# GeneralScheme.net
KiCad netlist of a schematic drawn in Altium Designer
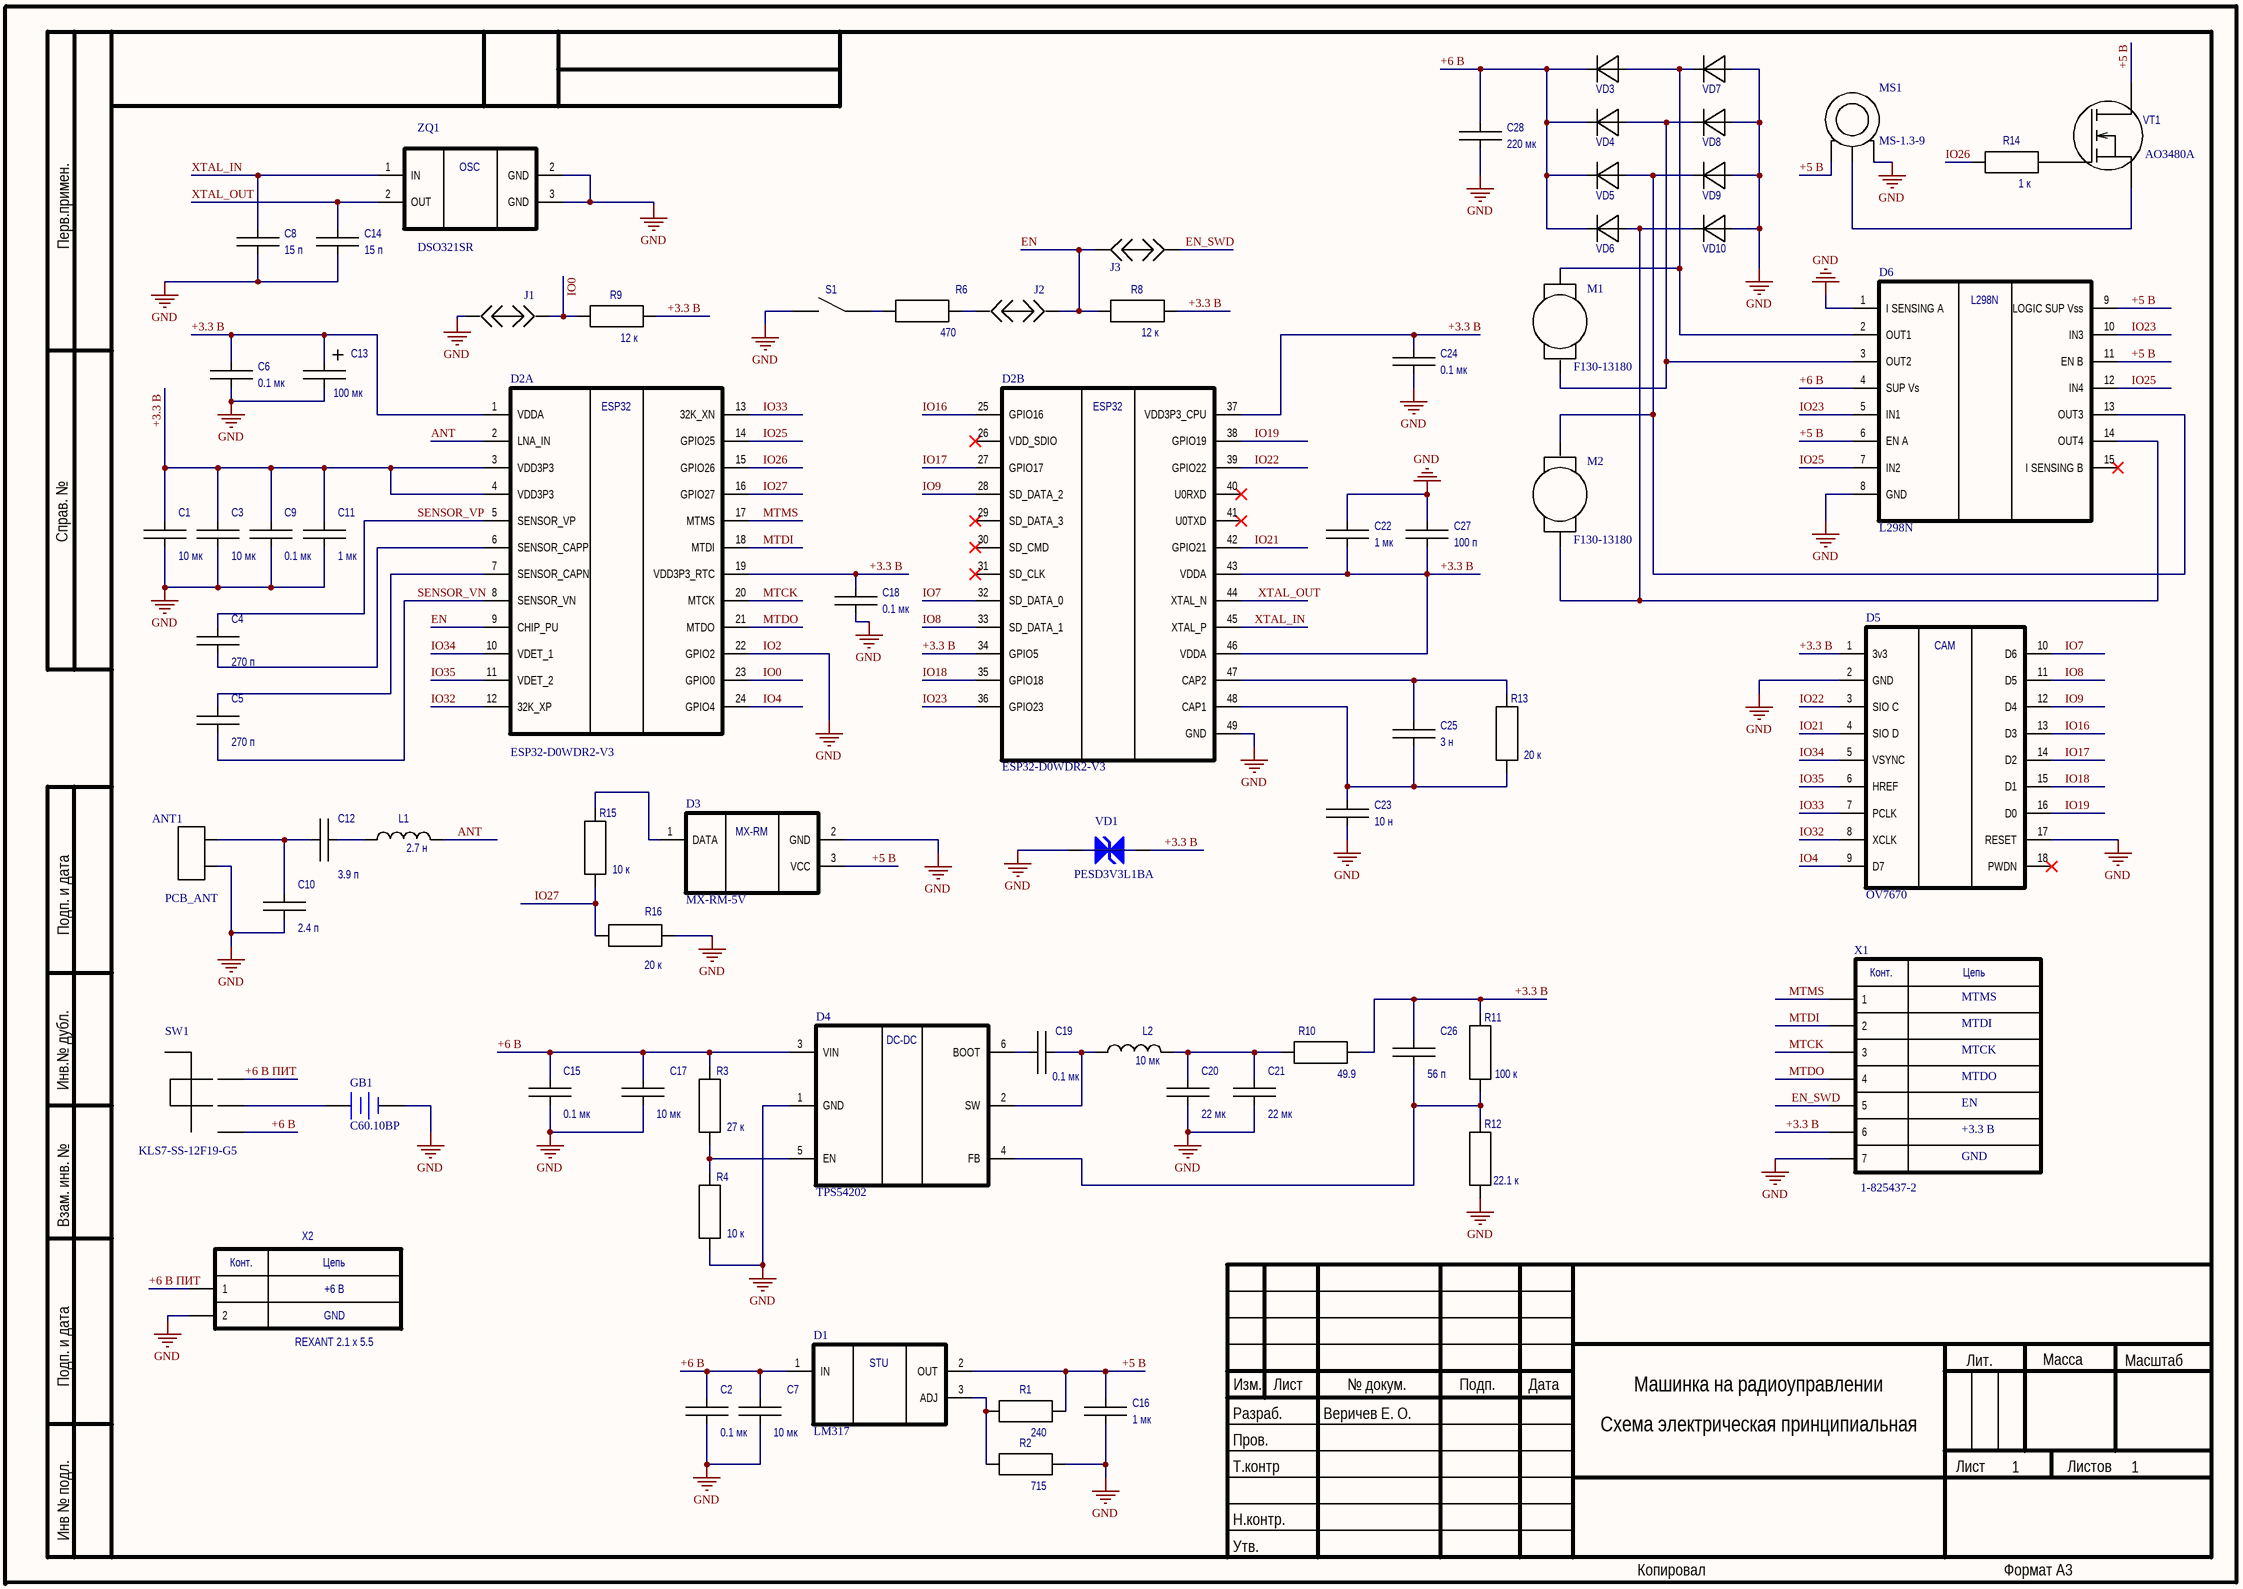
[diagram p0: GeneralScheme.SchDoc]

(export (version "E")
  (design (tool "Eeschema 10.0.6"))
  (components
    (comp (ref "ANT1") (value "PCB_ANT") (libsource (lib "IVT_LIB") (part "PCB_ant")))
    (comp (ref "C1")
      (value "10 мк")
      (fields (field (name "Comment") "10 мкФ ±* * * *, *"))
      (libsource (lib "IVT_LIB") (part "C - Конденсатор"))
    )
    (comp (ref "C2")
      (value "0.1 мк")
      (fields (field (name "Comment") "0.1 мкФ ±* * * *, *"))
      (libsource (lib "IVT_LIB") (part "C - Конденсатор"))
    )
    (comp (ref "C3")
      (value "10 мк")
      (fields (field (name "Comment") "10 мкФ ±* * * *, *"))
      (libsource (lib "IVT_LIB") (part "C - Конденсатор"))
    )
    (comp (ref "C4")
      (value "270 п")
      (fields (field (name "Comment") "270 пФ ±* * * *, *"))
      (libsource (lib "IVT_LIB") (part "C - Конденсатор"))
    )
    (comp (ref "C5")
      (value "270 п")
      (fields (field (name "Comment") "270 пФ ±* * * *, *"))
      (libsource (lib "IVT_LIB") (part "C - Конденсатор"))
    )
    (comp (ref "C6")
      (value "0.1 мк")
      (fields (field (name "Comment") "0.1 мкФ ±* * * *, *"))
      (libsource (lib "IVT_LIB") (part "C - Конденсатор"))
    )
    (comp (ref "C7")
      (value "10 мк")
      (fields (field (name "Comment") "10 мкФ ±* * * *, *"))
      (libsource (lib "IVT_LIB") (part "C - Конденсатор"))
    )
    (comp (ref "C8")
      (value "15 п")
      (fields (field (name "Comment") "15 пФ ±* * * *, *"))
      (libsource (lib "IVT_LIB") (part "C - Конденсатор"))
    )
    (comp (ref "C9")
      (value "0.1 мк")
      (fields (field (name "Comment") "0.1 мкФ ±* * * *, *"))
      (libsource (lib "IVT_LIB") (part "C - Конденсатор"))
    )
    (comp (ref "C10")
      (value "2.4 п")
      (fields (field (name "Comment") "2.4 пФ ±* * * *, *"))
      (libsource (lib "IVT_LIB") (part "C - Конденсатор"))
    )
    (comp (ref "C11")
      (value "1 мк")
      (fields (field (name "Comment") "1 мкФ ±* * * *, *"))
      (libsource (lib "IVT_LIB") (part "C - Конденсатор"))
    )
    (comp (ref "C12")
      (value "3.9 п")
      (fields (field (name "Comment") "3.9 пФ ±* * * *, *"))
      (libsource (lib "IVT_LIB") (part "C - Конденсатор"))
    )
    (comp (ref "C13")
      (value "100 мк")
      (fields (field (name "Comment") "100 мкФ ±* * * *, *"))
      (libsource (lib "IVT_LIB") (part "C+ - Конденсатор электролитический"))
    )
    (comp (ref "C14")
      (value "15 п")
      (fields (field (name "Comment") "15 пФ ±* * * *, *"))
      (libsource (lib "IVT_LIB") (part "C - Конденсатор"))
    )
    (comp (ref "C15")
      (value "0.1 мк")
      (fields (field (name "Comment") "0.1 мкФ ±* * * *, *"))
      (libsource (lib "IVT_LIB") (part "C - Конденсатор"))
    )
    (comp (ref "C16")
      (value "1 мк")
      (fields (field (name "Comment") "1 мкФ ±* * * *, *"))
      (libsource (lib "IVT_LIB") (part "C - Конденсатор"))
    )
    (comp (ref "C17")
      (value "10 мк")
      (fields (field (name "Comment") "10 мкФ ±* * * *, *"))
      (libsource (lib "IVT_LIB") (part "C - Конденсатор"))
    )
    (comp (ref "C18")
      (value "0.1 мк")
      (fields (field (name "Comment") "0.1 мкФ ±* * * *, *"))
      (libsource (lib "IVT_LIB") (part "C - Конденсатор"))
    )
    (comp (ref "C19")
      (value "0.1 мк")
      (fields (field (name "Comment") "0.1 мкФ ±* * * *, *"))
      (libsource (lib "IVT_LIB") (part "C - Конденсатор"))
    )
    (comp (ref "C20")
      (value "22 мк")
      (fields (field (name "Comment") "22 мкФ ±* * * *, *"))
      (libsource (lib "IVT_LIB") (part "C - Конденсатор"))
    )
    (comp (ref "C21")
      (value "22 мк")
      (fields (field (name "Comment") "22 мкФ ±* * * *, *"))
      (libsource (lib "IVT_LIB") (part "C - Конденсатор"))
    )
    (comp (ref "C22")
      (value "1 мк")
      (fields (field (name "Comment") "1 мкФ ±* * * *, *"))
      (libsource (lib "IVT_LIB") (part "C - Конденсатор"))
    )
    (comp (ref "C23")
      (value "10 н")
      (fields (field (name "Comment") "10 нФ ±* * * *, *"))
      (libsource (lib "IVT_LIB") (part "C - Конденсатор"))
    )
    (comp (ref "C24")
      (value "0.1 мк")
      (fields (field (name "Comment") "0.1 мкФ ±* * * *, *"))
      (libsource (lib "IVT_LIB") (part "C - Конденсатор"))
    )
    (comp (ref "C25")
      (value "3 н")
      (fields (field (name "Comment") "3 нФ ±* * * *, *"))
      (libsource (lib "IVT_LIB") (part "C - Конденсатор"))
    )
    (comp (ref "C26")
      (value "56 п")
      (fields (field (name "Comment") "56 пФ ±* * * *, *"))
      (libsource (lib "IVT_LIB") (part "C - Конденсатор"))
    )
    (comp (ref "C27")
      (value "100 п")
      (fields (field (name "Comment") "100 пФ ±* * * *, *"))
      (libsource (lib "IVT_LIB") (part "C - Конденсатор"))
    )
    (comp (ref "C28")
      (value "220 мк")
      (fields (field (name "Comment") "220 мкФ ±* * * *, *"))
      (libsource (lib "IVT_LIB") (part "C - Конденсатор"))
    )
    (comp (ref "D1") (value "LM317") (libsource (lib "IVT_LIB") (part "LM317")))
    (comp (ref "D2") (value "ESP32-D0WDR2-V3") (libsource (lib "IVT_LIB") (part "ESP32-D0WDR2-V3")))
    (comp (ref "D3") (value "MX-RM-5V") (libsource (lib "IVT_LIB") (part "MX-RM-5V_reciever_module")))
    (comp (ref "D4") (value "TPS54202") (libsource (lib "IVT_LIB") (part "TPS54202_DCDC")))
    (comp (ref "D5") (value "OV7670") (libsource (lib "IVT_LIB") (part "OV7670_module")))
    (comp (ref "D6") (value "L298N") (libsource (lib "IVT_LIB") (part "L298N")))
    (comp (ref "GB1")
      (value "C60.10BP")
      (footprint "BAT-2")
      (description "Multicell Battery")
      (fields (field (name "PUBLISHER") "Altium Limited"))
      (libsource (lib "Miscellaneous Devices") (part "Battery"))
    )
    (comp (ref "J1") (value "Jumper") (libsource (lib "IVT_LIB") (part "Jumper")))
    (comp (ref "J2") (value "Jumper") (libsource (lib "IVT_LIB") (part "Jumper")))
    (comp (ref "J3") (value "Jumper") (libsource (lib "IVT_LIB") (part "Jumper")))
    (comp (ref "L1") (value "2.7 н") (libsource (lib "IVT_LIB") (part "L - induct_my")))
    (comp (ref "L2") (value "10 мк") (libsource (lib "IVT_LIB") (part "L - induct_my")))
    (comp (ref "M1") (value "F130-13180") (libsource (lib "IVT_LIB") (part "F130-13180")))
    (comp (ref "M2") (value "F130-13180") (libsource (lib "IVT_LIB") (part "F130-13180")))
    (comp (ref "MS1") (value "MS-1.3-9") (libsource (lib "IVT_LIB") (part "MS-1.3-9")))
    (comp (ref "R1")
      (value "240")
      (fields (field (name "Comment") "240Ом ±* *, *"))
      (libsource (lib "IVT_LIB") (part "R - Резистор"))
    )
    (comp (ref "R2")
      (value "715")
      (fields (field (name "Comment") "715Ом ±* *, *"))
      (libsource (lib "IVT_LIB") (part "R - Резистор"))
    )
    (comp (ref "R3")
      (value "27 к")
      (fields (field (name "Comment") "27 кОм ±* *, *"))
      (libsource (lib "IVT_LIB") (part "R - Резистор"))
    )
    (comp (ref "R4")
      (value "10 к")
      (fields (field (name "Comment") "10 кОм ±* *, *"))
      (libsource (lib "IVT_LIB") (part "R - Резистор"))
    )
    (comp (ref "R6")
      (value "470")
      (fields (field (name "Comment") "470Ом ±* *, *"))
      (libsource (lib "IVT_LIB") (part "R - Резистор"))
    )
    (comp (ref "R8")
      (value "12 к")
      (fields (field (name "Comment") "12 кОм ±* *, *"))
      (libsource (lib "IVT_LIB") (part "R - Резистор"))
    )
    (comp (ref "R9")
      (value "12 к")
      (fields (field (name "Comment") "12 кОм ±* *, *"))
      (libsource (lib "IVT_LIB") (part "R - Резистор"))
    )
    (comp (ref "R10")
      (value "49.9")
      (fields (field (name "Comment") "49.9Ом ±* *, *"))
      (libsource (lib "IVT_LIB") (part "R - Резистор"))
    )
    (comp (ref "R11")
      (value "100 к")
      (fields (field (name "Comment") "100 кОм ±* *, *"))
      (libsource (lib "IVT_LIB") (part "R - Резистор"))
    )
    (comp (ref "R12")
      (value "22.1 к")
      (fields (field (name "Comment") "22.1 кОм ±* *, *"))
      (libsource (lib "IVT_LIB") (part "R - Резистор"))
    )
    (comp (ref "R13")
      (value "20 к")
      (fields (field (name "Comment") "20 кОм ±* *, *"))
      (libsource (lib "IVT_LIB") (part "R - Резистор"))
    )
    (comp (ref "R14")
      (value "1 к")
      (fields (field (name "Comment") "1 кОм ±* *, *"))
      (libsource (lib "IVT_LIB") (part "R - Резистор"))
    )
    (comp (ref "R15")
      (value "10 к")
      (fields (field (name "Comment") "10 кОм ±* *, *"))
      (libsource (lib "IVT_LIB") (part "R - Резистор"))
    )
    (comp (ref "R16")
      (value "20 к")
      (fields (field (name "Comment") "20 кОм ±* *, *"))
      (libsource (lib "IVT_LIB") (part "R - Резистор"))
    )
    (comp (ref "S1")
      (value "Тактильный переключатель KLS7-TS6604-4.3-180-B KLS")
      (fields (field (name "PARTNUMBER") "KLS7-TS6604-4.3-180-B"))
      (libsource (lib "IVT_LIB") (part "S - Кнопка тактовая"))
    )
    (comp (ref "SW1") (value "KLS7-SS-12F19-G5") (libsource (lib "IVT_LIB") (part "Switch")))
    (comp (ref "VD1")
      (value "PESD3V3L1BA")
      (footprint "DIODE-0.7")
      (description "Zener Diode")
      (fields (field (name "PUBLISHER") "Altium Limited"))
      (libsource (lib "Miscellaneous Devices") (part "D Zener"))
    )
    (comp (ref "VD2")
      (value "D Zener")
      (footprint "DIODE-0.7")
      (description "Zener Diode")
      (fields (field (name "PUBLISHER") "Altium Limited"))
      (libsource (lib "Miscellaneous Devices") (part "D Zener"))
    )
    (comp (ref "VD3") (value "MBR0540") (libsource (lib "IVT_LIB") (part "VD - Диод обычный")))
    (comp (ref "VD4") (value "MBR0540") (libsource (lib "IVT_LIB") (part "VD - Диод обычный")))
    (comp (ref "VD5") (value "MBR0540") (libsource (lib "IVT_LIB") (part "VD - Диод обычный")))
    (comp (ref "VD6") (value "MBR0540") (libsource (lib "IVT_LIB") (part "VD - Диод обычный")))
    (comp (ref "VD7") (value "MBR0540") (libsource (lib "IVT_LIB") (part "VD - Диод обычный")))
    (comp (ref "VD8") (value "MBR0540") (libsource (lib "IVT_LIB") (part "VD - Диод обычный")))
    (comp (ref "VD9") (value "MBR0540") (libsource (lib "IVT_LIB") (part "VD - Диод обычный")))
    (comp (ref "VD10") (value "MBR0540") (libsource (lib "IVT_LIB") (part "VD - Диод обычный")))
    (comp (ref "VT1")
      (value "AO3480A")
      (description "VT")
      (libsource (lib "IVT_LIB") (part "VT - Полевой транзистор N канал (MOSFET_N)"))
    )
    (comp (ref "X1")
      (value "1-825437-2")
      (fields
        (field (name "PARAMETER 7") "GND")
        (field (name "PARAMETER 6") "+3.3 В")
        (field (name "PARAMETER 2") "MTDI")
        (field (name "PARAMETER 5") "EN")
        (field (name "PARAMETER 4") "MTDO")
        (field (name "PARAMETER 3") "MTCK")
        (field (name "PARAMETER 1") "MTMS")
      )
      (libsource (lib "IVT_LIB") (part "X - контактное поле х7"))
    )
    (comp (ref "X2")
      (value "REXANT 2.1 х 5.5")
      (fields (field (name "1") "+6 В") (field (name "2") "GND"))
      (libsource (lib "IVT_LIB") (part "X - Контактное поле х2"))
    )
    (comp (ref "ZQ1") (value "DSO321SR") (libsource (lib "IVT_LIB") (part "DSO321SR_oscill")))
  )
  (nets
    (net (code "1") (name "/+3.3 В") (class "Default")
      (node (ref "C1") (pin "2") (pinfunction "2_2") (pintype "passive"))
      (node (ref "C11") (pin "2") (pinfunction "2_2") (pintype "passive"))
      (node (ref "C13") (pin "1") (pinfunction "1_1") (pintype "passive"))
      (node (ref "C18") (pin "2") (pinfunction "2_2") (pintype "passive"))
      (node (ref "C22") (pin "1") (pinfunction "1_1") (pintype "passive"))
      (node (ref "C24") (pin "2") (pinfunction "2_2") (pintype "passive"))
      (node (ref "C26") (pin "2") (pinfunction "2_2") (pintype "passive"))
      (node (ref "C27") (pin "1") (pinfunction "1_1") (pintype "passive"))
      (node (ref "C3") (pin "2") (pinfunction "2_2") (pintype "passive"))
      (node (ref "C6") (pin "2") (pinfunction "2_2") (pintype "passive"))
      (node (ref "C9") (pin "2") (pinfunction "2_2") (pintype "passive"))
      (node (ref "D2") (pin "1") (pinfunction "VDDA_1") (pintype "passive"))
      (node (ref "D2") (pin "19") (pinfunction "VDD3P3_RTC_19") (pintype "passive"))
      (node (ref "D2") (pin "3") (pinfunction "VDD3P3_3") (pintype "passive"))
      (node (ref "D2") (pin "34") (pinfunction "GPIO5_34") (pintype "passive"))
      (node (ref "D2") (pin "37") (pinfunction "VDD3P3_CPU_37") (pintype "passive"))
      (node (ref "D2") (pin "4") (pinfunction "VDD3P3_4") (pintype "passive"))
      (node (ref "D2") (pin "43") (pinfunction "VDDA_43") (pintype "passive"))
      (node (ref "D2") (pin "46") (pinfunction "VDDA_46") (pintype "passive"))
      (node (ref "D5") (pin "1") (pinfunction "3v3_1") (pintype "passive"))
      (node (ref "R10") (pin "1") (pinfunction "1_1") (pintype "passive"))
      (node (ref "R11") (pin "2") (pinfunction "2_2") (pintype "passive"))
      (node (ref "R8") (pin "2") (pinfunction "2_2") (pintype "passive"))
      (node (ref "R9") (pin "2") (pinfunction "2_2") (pintype "passive"))
      (node (ref "VD2") (pin "1") (pinfunction "A_1") (pintype "passive"))
      (node (ref "X1") (pin "6") (pinfunction "6_6") (pintype "passive"))
    )
    (net (code "2") (name "/+5 В") (class "Default")
      (node (ref "C16") (pin "2") (pinfunction "2_2") (pintype "passive"))
      (node (ref "D1") (pin "2") (pinfunction "OUT_2") (pintype "passive"))
      (node (ref "D3") (pin "3") (pinfunction "VCC_3") (pintype "passive"))
      (node (ref "D6") (pin "11") (pinfunction "EN_B_11") (pintype "passive"))
      (node (ref "D6") (pin "6") (pinfunction "EN_A_6") (pintype "passive"))
      (node (ref "D6") (pin "9") (pinfunction "LOGIC_SUP_Vss_9") (pintype "passive"))
      (node (ref "MS1") (pin "1") (pinfunction "VDD_1") (pintype "passive"))
      (node (ref "R1") (pin "1") (pinfunction "1_1") (pintype "passive"))
      (node (ref "VT1") (pin "1") (pintype "passive"))
    )
    (net (code "3") (name "/+6 В") (class "Default")
      (node (ref "C15") (pin "2") (pinfunction "2_2") (pintype "passive"))
      (node (ref "C17") (pin "2") (pinfunction "2_2") (pintype "passive"))
      (node (ref "C2") (pin "2") (pinfunction "2_2") (pintype "passive"))
      (node (ref "C28") (pin "2") (pinfunction "2_2") (pintype "passive"))
      (node (ref "C7") (pin "2") (pinfunction "2_2") (pintype "passive"))
      (node (ref "D1") (pin "1") (pinfunction "IN_1") (pintype "passive"))
      (node (ref "D4") (pin "3") (pinfunction "VIN_3") (pintype "passive"))
      (node (ref "D6") (pin "4") (pinfunction "SUP_Vs_4") (pintype "passive"))
      (node (ref "R3") (pin "2") (pinfunction "2_2") (pintype "passive"))
      (node (ref "SW1") (pin "3") (pinfunction "3_3") (pintype "passive"))
      (node (ref "VD3") (pin "1") (pinfunction "C_1") (pintype "passive"))
      (node (ref "VD4") (pin "1") (pinfunction "C_1") (pintype "passive"))
      (node (ref "VD5") (pin "1") (pinfunction "C_1") (pintype "passive"))
      (node (ref "VD6") (pin "1") (pinfunction "C_1") (pintype "passive"))
    )
    (net (code "4") (name "/+6 В ПИТ") (class "Default")
      (node (ref "SW1") (pin "1") (pinfunction "1_1") (pintype "passive"))
      (node (ref "X2") (pin "1") (pinfunction "1_1") (pintype "passive"))
    )
    (net (code "5") (name "/ANT") (class "Default")
      (node (ref "D2") (pin "2") (pinfunction "LNA_IN_2") (pintype "passive"))
      (node (ref "L1") (pin "1") (pinfunction "1_1") (pintype "passive"))
    )
    (net (code "6") (name "/EN") (class "Default")
      (node (ref "D2") (pin "9") (pinfunction "CHIP_PU_9") (pintype "passive"))
      (node (ref "J2") (pin "2") (pinfunction "2_2") (pintype "passive"))
      (node (ref "J3") (pin "2") (pinfunction "2_2") (pintype "passive"))
      (node (ref "R8") (pin "1") (pinfunction "1_1") (pintype "passive"))
    )
    (net (code "7") (name "/EN_SWD") (class "Default")
      (node (ref "J3") (pin "1") (pinfunction "1_1") (pintype "passive"))
      (node (ref "X1") (pin "5") (pinfunction "5_5") (pintype "passive"))
    )
    (net (code "8") (name "/IO0") (class "Default")
      (node (ref "D2") (pin "23") (pinfunction "GPIO0_23") (pintype "passive"))
      (node (ref "J1") (pin "2") (pinfunction "2_2") (pintype "passive"))
      (node (ref "R9") (pin "1") (pinfunction "1_1") (pintype "passive"))
    )
    (net (code "9") (name "/IO4") (class "Default")
      (node (ref "D2") (pin "24") (pinfunction "GPIO4_24") (pintype "passive"))
      (node (ref "D5") (pin "9") (pinfunction "D7_9") (pintype "passive"))
    )
    (net (code "10") (name "/IO7") (class "Default")
      (node (ref "D2") (pin "32") (pinfunction "SD_DATA_0_32") (pintype "passive"))
      (node (ref "D5") (pin "10") (pinfunction "D6_10") (pintype "passive"))
    )
    (net (code "11") (name "/IO8") (class "Default")
      (node (ref "D2") (pin "33") (pinfunction "SD_DATA_1_33") (pintype "passive"))
      (node (ref "D5") (pin "11") (pinfunction "D5_11") (pintype "passive"))
    )
    (net (code "12") (name "/IO9") (class "Default")
      (node (ref "D2") (pin "28") (pinfunction "SD_DATA_2_28") (pintype "passive"))
      (node (ref "D5") (pin "12") (pinfunction "D4_12") (pintype "passive"))
    )
    (net (code "13") (name "/IO16") (class "Default")
      (node (ref "D2") (pin "25") (pinfunction "GPIO16_25") (pintype "passive"))
      (node (ref "D5") (pin "13") (pinfunction "D3_13") (pintype "passive"))
    )
    (net (code "14") (name "/IO17") (class "Default")
      (node (ref "D2") (pin "27") (pinfunction "GPIO17_27") (pintype "passive"))
      (node (ref "D5") (pin "14") (pinfunction "D2_14") (pintype "passive"))
    )
    (net (code "15") (name "/IO18") (class "Default")
      (node (ref "D2") (pin "35") (pinfunction "GPIO18_35") (pintype "passive"))
      (node (ref "D5") (pin "15") (pinfunction "D1_15") (pintype "passive"))
    )
    (net (code "16") (name "/IO19") (class "Default")
      (node (ref "D2") (pin "38") (pinfunction "GPIO19_38") (pintype "passive"))
      (node (ref "D5") (pin "16") (pinfunction "D0_16") (pintype "passive"))
    )
    (net (code "17") (name "/IO21") (class "Default")
      (node (ref "D2") (pin "42") (pinfunction "GPIO21_42") (pintype "passive"))
      (node (ref "D5") (pin "4") (pinfunction "SIO_D_4") (pintype "passive"))
    )
    (net (code "18") (name "/IO22") (class "Default")
      (node (ref "D2") (pin "39") (pinfunction "GPIO22_39") (pintype "passive"))
      (node (ref "D5") (pin "3") (pinfunction "SIO_C_3") (pintype "passive"))
    )
    (net (code "19") (name "/IO23") (class "Default")
      (node (ref "D2") (pin "36") (pinfunction "GPIO23_36") (pintype "passive"))
      (node (ref "D6") (pin "10") (pinfunction "IN3_10") (pintype "passive"))
      (node (ref "D6") (pin "5") (pinfunction "IN1_5") (pintype "passive"))
    )
    (net (code "20") (name "/IO25") (class "Default")
      (node (ref "D2") (pin "14") (pinfunction "GPIO25_14") (pintype "passive"))
      (node (ref "D6") (pin "12") (pinfunction "IN4_12") (pintype "passive"))
      (node (ref "D6") (pin "7") (pinfunction "IN2_7") (pintype "passive"))
    )
    (net (code "21") (name "/IO26") (class "Default")
      (node (ref "D2") (pin "15") (pinfunction "GPIO26_15") (pintype "passive"))
      (node (ref "R14") (pin "1") (pinfunction "1_1") (pintype "passive"))
    )
    (net (code "22") (name "/IO27") (class "Default")
      (node (ref "D2") (pin "16") (pinfunction "GPIO27_16") (pintype "passive"))
      (node (ref "R15") (pin "1") (pinfunction "1_1") (pintype "passive"))
      (node (ref "R16") (pin "2") (pinfunction "2_2") (pintype "passive"))
    )
    (net (code "23") (name "/IO32") (class "Default")
      (node (ref "D2") (pin "12") (pinfunction "32K_XP_12") (pintype "passive"))
      (node (ref "D5") (pin "8") (pinfunction "XCLK_8") (pintype "passive"))
    )
    (net (code "24") (name "/IO33") (class "Default")
      (node (ref "D2") (pin "13") (pinfunction "32K_XN_13") (pintype "passive"))
      (node (ref "D5") (pin "7") (pinfunction "PCLK_7") (pintype "passive"))
    )
    (net (code "25") (name "/IO34") (class "Default")
      (node (ref "D2") (pin "10") (pinfunction "VDET_1_10") (pintype "passive"))
      (node (ref "D5") (pin "5") (pinfunction "VSYNC_5") (pintype "passive"))
    )
    (net (code "26") (name "/IO35") (class "Default")
      (node (ref "D2") (pin "11") (pinfunction "VDET_2_11") (pintype "passive"))
      (node (ref "D5") (pin "6") (pinfunction "HREF_6") (pintype "passive"))
    )
    (net (code "27") (name "/MTCK") (class "Default")
      (node (ref "D2") (pin "20") (pinfunction "MTCK_20") (pintype "passive"))
      (node (ref "X1") (pin "3") (pinfunction "3_3") (pintype "passive"))
    )
    (net (code "28") (name "/MTDI") (class "Default")
      (node (ref "D2") (pin "18") (pinfunction "MTDI_18") (pintype "passive"))
      (node (ref "X1") (pin "2") (pinfunction "2_2") (pintype "passive"))
    )
    (net (code "29") (name "/MTDO") (class "Default")
      (node (ref "D2") (pin "21") (pinfunction "MTDO_21") (pintype "passive"))
      (node (ref "X1") (pin "4") (pinfunction "4_4") (pintype "passive"))
    )
    (net (code "30") (name "/MTMS") (class "Default")
      (node (ref "D2") (pin "17") (pinfunction "MTMS_17") (pintype "passive"))
      (node (ref "X1") (pin "1") (pinfunction "1_1") (pintype "passive"))
    )
    (net (code "31") (name "/SENSOR_VN") (class "Default")
      (node (ref "C5") (pin "1") (pinfunction "1_1") (pintype "passive"))
      (node (ref "D2") (pin "8") (pinfunction "SENSOR_VN_8") (pintype "passive"))
    )
    (net (code "32") (name "/SENSOR_VP") (class "Default")
      (node (ref "C4") (pin "2") (pinfunction "2_2") (pintype "passive"))
      (node (ref "D2") (pin "5") (pinfunction "SENSOR_VP_5") (pintype "passive"))
    )
    (net (code "33") (name "/XTAL_IN") (class "Default")
      (node (ref "C8") (pin "2") (pinfunction "2_2") (pintype "passive"))
      (node (ref "D2") (pin "45") (pinfunction "XTAL_P_45") (pintype "passive"))
      (node (ref "ZQ1") (pin "1") (pinfunction "IN_1") (pintype "passive"))
    )
    (net (code "34") (name "/XTAL_OUT") (class "Default")
      (node (ref "C14") (pin "2") (pinfunction "2_2") (pintype "passive"))
      (node (ref "D2") (pin "44") (pinfunction "XTAL_N_44") (pintype "passive"))
      (node (ref "ZQ1") (pin "2") (pinfunction "OUT_2") (pintype "passive"))
    )
    (net (code "35") (name "GND") (class "Default")
      (node (ref "ANT1") (pin "2") (pinfunction "2_2") (pintype "passive"))
      (node (ref "C1") (pin "1") (pinfunction "1_1") (pintype "passive"))
      (node (ref "C10") (pin "1") (pinfunction "1_1") (pintype "passive"))
      (node (ref "C11") (pin "1") (pinfunction "1_1") (pintype "passive"))
      (node (ref "C13") (pin "2") (pinfunction "2_2") (pintype "passive"))
      (node (ref "C14") (pin "1") (pinfunction "1_1") (pintype "passive"))
      (node (ref "C15") (pin "1") (pinfunction "1_1") (pintype "passive"))
      (node (ref "C16") (pin "1") (pinfunction "1_1") (pintype "passive"))
      (node (ref "C17") (pin "1") (pinfunction "1_1") (pintype "passive"))
      (node (ref "C18") (pin "1") (pinfunction "1_1") (pintype "passive"))
      (node (ref "C2") (pin "1") (pinfunction "1_1") (pintype "passive"))
      (node (ref "C20") (pin "1") (pinfunction "1_1") (pintype "passive"))
      (node (ref "C21") (pin "1") (pinfunction "1_1") (pintype "passive"))
      (node (ref "C22") (pin "2") (pinfunction "2_2") (pintype "passive"))
      (node (ref "C23") (pin "1") (pinfunction "1_1") (pintype "passive"))
      (node (ref "C24") (pin "1") (pinfunction "1_1") (pintype "passive"))
      (node (ref "C27") (pin "2") (pinfunction "2_2") (pintype "passive"))
      (node (ref "C28") (pin "1") (pinfunction "1_1") (pintype "passive"))
      (node (ref "C3") (pin "1") (pinfunction "1_1") (pintype "passive"))
      (node (ref "C6") (pin "1") (pinfunction "1_1") (pintype "passive"))
      (node (ref "C7") (pin "1") (pinfunction "1_1") (pintype "passive"))
      (node (ref "C8") (pin "1") (pinfunction "1_1") (pintype "passive"))
      (node (ref "C9") (pin "1") (pinfunction "1_1") (pintype "passive"))
      (node (ref "D2") (pin "22") (pinfunction "GPIO2_22") (pintype "passive"))
      (node (ref "D2") (pin "49") (pinfunction "GND_49") (pintype "passive"))
      (node (ref "D3") (pin "2") (pinfunction "GND_2") (pintype "passive"))
      (node (ref "D4") (pin "1") (pinfunction "GND_1") (pintype "passive"))
      (node (ref "D5") (pin "17") (pinfunction "RESET_17") (pintype "passive"))
      (node (ref "D5") (pin "2") (pinfunction "GND_2") (pintype "passive"))
      (node (ref "D6") (pin "1") (pinfunction "I_SENSING_A_1") (pintype "passive"))
      (node (ref "D6") (pin "8") (pinfunction "GND_8") (pintype "passive"))
      (node (ref "GB1") (pin "2") (pinfunction "-_2") (pintype "passive"))
      (node (ref "J1") (pin "1") (pinfunction "1_1") (pintype "passive"))
      (node (ref "MS1") (pin "2") (pinfunction "GND_2") (pintype "passive"))
      (node (ref "R12") (pin "1") (pinfunction "1_1") (pintype "passive"))
      (node (ref "R16") (pin "1") (pinfunction "1_1") (pintype "passive"))
      (node (ref "R2") (pin "1") (pinfunction "1_1") (pintype "passive"))
      (node (ref "R4") (pin "1") (pinfunction "1_1") (pintype "passive"))
      (node (ref "S1") (pin "4") (pinfunction "4_4") (pintype "passive"))
      (node (ref "VD1") (pin "1") (pinfunction "A_1") (pintype "passive"))
      (node (ref "VD10") (pin "1") (pinfunction "A_1") (pintype "passive"))
      (node (ref "VD7") (pin "1") (pinfunction "A_1") (pintype "passive"))
      (node (ref "VD8") (pin "1") (pinfunction "A_1") (pintype "passive"))
      (node (ref "VD9") (pin "1") (pinfunction "A_1") (pintype "passive"))
      (node (ref "X1") (pin "7") (pinfunction "7_7") (pintype "passive"))
      (node (ref "X2") (pin "2") (pinfunction "2_2") (pintype "passive"))
      (node (ref "ZQ1") (pin "2") (pinfunction "GND_2") (pintype "passive"))
      (node (ref "ZQ1") (pin "3") (pinfunction "GND_3") (pintype "passive"))
    )
    (net (code "36") (name "Net-(ANT1-Pad1)") (class "Default")
      (node (ref "ANT1") (pin "1") (pinfunction "1_1") (pintype "passive"))
      (node (ref "C10") (pin "2") (pinfunction "2_2") (pintype "passive"))
      (node (ref "C12") (pin "2") (pinfunction "2_2") (pintype "passive"))
    )
    (net (code "37") (name "Net-(C12-Pad1)") (class "Default")
      (node (ref "C12") (pin "1") (pinfunction "1_1") (pintype "passive"))
      (node (ref "L1") (pin "2") (pinfunction "2_2") (pintype "passive"))
    )
    (net (code "38") (name "Net-(C20-Pad2)") (class "Default")
      (node (ref "C20") (pin "2") (pinfunction "2_2") (pintype "passive"))
      (node (ref "C21") (pin "2") (pinfunction "2_2") (pintype "passive"))
      (node (ref "L2") (pin "1") (pinfunction "1_1") (pintype "passive"))
      (node (ref "R10") (pin "2") (pinfunction "2_2") (pintype "passive"))
    )
    (net (code "39") (name "Net-(D1-ADJ)") (class "Default")
      (node (ref "D1") (pin "3") (pinfunction "ADJ_3") (pintype "passive"))
      (node (ref "R1") (pin "2") (pinfunction "2_2") (pintype "passive"))
      (node (ref "R2") (pin "2") (pinfunction "2_2") (pintype "passive"))
    )
    (net (code "40") (name "Net-(D2A-SENSOR_CAPN)") (class "Default")
      (node (ref "C5") (pin "2") (pinfunction "2_2") (pintype "passive"))
      (node (ref "D2") (pin "7") (pinfunction "SENSOR_CAPN_7") (pintype "passive"))
    )
    (net (code "41") (name "Net-(D2A-SENSOR_CAPP)") (class "Default")
      (node (ref "C4") (pin "1") (pinfunction "1_1") (pintype "passive"))
      (node (ref "D2") (pin "6") (pinfunction "SENSOR_CAPP_6") (pintype "passive"))
    )
    (net (code "42") (name "Net-(D2B-CAP1)") (class "Default")
      (node (ref "C23") (pin "2") (pinfunction "2_2") (pintype "passive"))
      (node (ref "C25") (pin "1") (pinfunction "1_1") (pintype "passive"))
      (node (ref "D2") (pin "48") (pinfunction "CAP1_48") (pintype "passive"))
      (node (ref "R13") (pin "1") (pinfunction "1_1") (pintype "passive"))
    )
    (net (code "43") (name "Net-(D2B-CAP2)") (class "Default")
      (node (ref "C25") (pin "2") (pinfunction "2_2") (pintype "passive"))
      (node (ref "D2") (pin "47") (pinfunction "CAP2_47") (pintype "passive"))
      (node (ref "R13") (pin "2") (pinfunction "2_2") (pintype "passive"))
    )
    (net (code "44") (name "Net-(D3-DATA)") (class "Default")
      (node (ref "D3") (pin "1") (pinfunction "DATA_1") (pintype "passive"))
      (node (ref "R15") (pin "2") (pinfunction "2_2") (pintype "passive"))
    )
    (net (code "45") (name "Net-(D4-BOOT)") (class "Default")
      (node (ref "C19") (pin "2") (pinfunction "2_2") (pintype "passive"))
      (node (ref "D4") (pin "6") (pinfunction "BOOT_6") (pintype "passive"))
    )
    (net (code "46") (name "Net-(D4-EN)") (class "Default")
      (node (ref "D4") (pin "5") (pinfunction "EN_5") (pintype "passive"))
      (node (ref "R3") (pin "1") (pinfunction "1_1") (pintype "passive"))
      (node (ref "R4") (pin "2") (pinfunction "2_2") (pintype "passive"))
    )
    (net (code "47") (name "Net-(D4-FB)") (class "Default")
      (node (ref "C26") (pin "1") (pinfunction "1_1") (pintype "passive"))
      (node (ref "D4") (pin "4") (pinfunction "FB_4") (pintype "passive"))
      (node (ref "R11") (pin "1") (pinfunction "1_1") (pintype "passive"))
      (node (ref "R12") (pin "2") (pinfunction "2_2") (pintype "passive"))
    )
    (net (code "48") (name "Net-(D4-SW)") (class "Default")
      (node (ref "C19") (pin "1") (pinfunction "1_1") (pintype "passive"))
      (node (ref "D4") (pin "2") (pinfunction "SW_2") (pintype "passive"))
      (node (ref "L2") (pin "2") (pinfunction "2_2") (pintype "passive"))
    )
    (net (code "49") (name "Net-(D6-OUT1)") (class "Default")
      (node (ref "D6") (pin "2") (pinfunction "OUT1_2") (pintype "passive"))
      (node (ref "M1") (pin "1") (pinfunction "1_1") (pintype "passive"))
      (node (ref "VD3") (pin "1") (pinfunction "A_1") (pintype "passive"))
      (node (ref "VD7") (pin "1") (pinfunction "C_1") (pintype "passive"))
    )
    (net (code "50") (name "Net-(D6-OUT2)") (class "Default")
      (node (ref "D6") (pin "3") (pinfunction "OUT2_3") (pintype "passive"))
      (node (ref "M1") (pin "2") (pinfunction "2_2") (pintype "passive"))
      (node (ref "VD4") (pin "1") (pinfunction "A_1") (pintype "passive"))
      (node (ref "VD8") (pin "1") (pinfunction "C_1") (pintype "passive"))
    )
    (net (code "51") (name "Net-(D6-OUT3)") (class "Default")
      (node (ref "D6") (pin "13") (pinfunction "OUT3_13") (pintype "passive"))
      (node (ref "M2") (pin "1") (pinfunction "1_1") (pintype "passive"))
      (node (ref "VD5") (pin "1") (pinfunction "A_1") (pintype "passive"))
      (node (ref "VD9") (pin "1") (pinfunction "C_1") (pintype "passive"))
    )
    (net (code "52") (name "Net-(D6-OUT4)") (class "Default")
      (node (ref "D6") (pin "14") (pinfunction "OUT4_14") (pintype "passive"))
      (node (ref "M2") (pin "2") (pinfunction "2_2") (pintype "passive"))
      (node (ref "VD10") (pin "1") (pinfunction "C_1") (pintype "passive"))
      (node (ref "VD6") (pin "1") (pinfunction "A_1") (pintype "passive"))
    )
    (net (code "53") (name "Net-(GB1-+)") (class "Default")
      (node (ref "GB1") (pin "1") (pinfunction "+_1") (pintype "passive"))
      (node (ref "SW1") (pin "2") (pinfunction "2_2") (pintype "passive"))
    )
    (net (code "54") (name "Net-(J2-Pad1)") (class "Default")
      (node (ref "J2") (pin "1") (pinfunction "1_1") (pintype "passive"))
      (node (ref "R6") (pin "2") (pinfunction "2_2") (pintype "passive"))
    )
    (net (code "55") (name "Net-(MS1-CNTRL)") (class "Default")
      (node (ref "MS1") (pin "2") (pinfunction "CNTRL_2") (pintype "passive"))
      (node (ref "VT1") (pin "2") (pintype "passive"))
    )
    (net (code "56") (name "Net-(R6-Pad1)") (class "Default")
      (node (ref "R6") (pin "1") (pinfunction "1_1") (pintype "passive"))
      (node (ref "S1") (pin "2") (pinfunction "2_2") (pintype "passive"))
    )
    (net (code "57") (name "Net-(R14-Pad2)") (class "Default")
      (node (ref "R14") (pin "2") (pinfunction "2_2") (pintype "passive"))
      (node (ref "VT1") (pin "3") (pintype "passive"))
    )
    (net (code "58") (name "Net-(VD1-K)") (class "Default")
      (node (ref "VD1") (pin "2") (pinfunction "K_2") (pintype "passive"))
      (node (ref "VD2") (pin "2") (pinfunction "K_2") (pintype "passive"))
    )
    (net (code "59") (name "unconnected-(D2B-SD_CLK-Pad31)") (class "Default")
      (node (ref "D2") (pin "31") (pinfunction "SD_CLK_31") (pintype "passive+no_connect"))
    )
    (net (code "60") (name "unconnected-(D2B-SD_CMD-Pad30)") (class "Default")
      (node (ref "D2") (pin "30") (pinfunction "SD_CMD_30") (pintype "passive+no_connect"))
    )
    (net (code "61") (name "unconnected-(D2B-SD_DATA_3-Pad29)") (class "Default")
      (node (ref "D2") (pin "29") (pinfunction "SD_DATA_3_29") (pintype "passive+no_connect"))
    )
    (net (code "62") (name "unconnected-(D2B-U0RXD-Pad40)") (class "Default")
      (node (ref "D2") (pin "40") (pinfunction "U0RXD_40") (pintype "passive+no_connect"))
    )
    (net (code "63") (name "unconnected-(D2B-U0TXD-Pad41)") (class "Default")
      (node (ref "D2") (pin "41") (pinfunction "U0TXD_41") (pintype "passive+no_connect"))
    )
    (net (code "64") (name "unconnected-(D2B-VDD_SDIO-Pad26)") (class "Default")
      (node (ref "D2") (pin "26") (pinfunction "VDD_SDIO_26") (pintype "passive+no_connect"))
    )
    (net (code "65") (name "unconnected-(D5-PWDN-Pad18)") (class "Default")
      (node (ref "D5") (pin "18") (pinfunction "PWDN_18") (pintype "passive+no_connect"))
    )
    (net (code "66") (name "unconnected-(D6-I_SENSING_B-Pad15)") (class "Default")
      (node (ref "D6") (pin "15") (pinfunction "I_SENSING_B_15") (pintype "passive+no_connect"))
    )
    (net (code "67") (name "unconnected-(SW1-Pad01)") (class "Default")
      (node (ref "SW1") (pin "01") (pinfunction "01_01") (pintype "passive"))
    )
  )
)
